# mouseaid.net
KiCad netlist of a schematic drawn in EAGLE
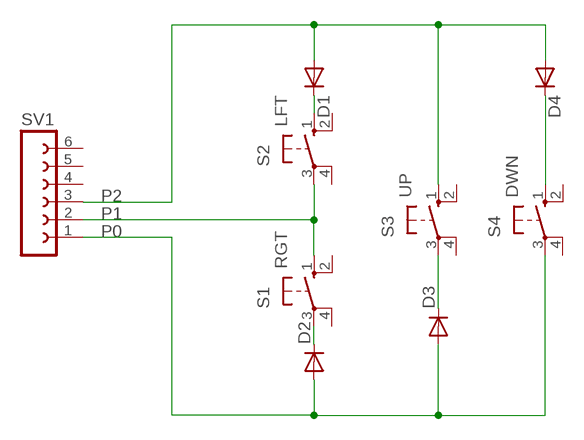
[diagram p0: schematic, sheet 1]

(export (version "E")
  (design (tool "Eeschema 10.0.6"))
  (components
    (comp (ref "D1")
      (value "DIODE-D-7.5")
      (footprint "eagle-import:D-7.5")
      (libsource (lib "eagle-import") (part "DIODE-D-7.5"))
    )
    (comp (ref "D2")
      (value "DIODE-D-7.5")
      (footprint "eagle-import:D-7.5")
      (libsource (lib "eagle-import") (part "DIODE-D-7.5"))
    )
    (comp (ref "D3")
      (value "DIODE-D-7.5")
      (footprint "eagle-import:D-7.5")
      (libsource (lib "eagle-import") (part "DIODE-D-7.5"))
    )
    (comp (ref "D4")
      (value "DIODE-D-7.5")
      (footprint "eagle-import:D-7.5")
      (libsource (lib "eagle-import") (part "DIODE-D-7.5"))
    )
    (comp (ref "S1")
      (value "RGT")
      (footprint "eagle-import:B3F-40XX")
      (fields (field (name "MF") "OMRON COMPONENTS USA") (field (name "MPN") "B3F-4000"))
      (libsource (lib "eagle-import") (part "40-XX"))
    )
    (comp (ref "S2")
      (value "LFT")
      (footprint "eagle-import:B3F-40XX")
      (fields (field (name "MF") "OMRON COMPONENTS USA") (field (name "MPN") "B3F-4000"))
      (libsource (lib "eagle-import") (part "40-XX"))
    )
    (comp (ref "S3")
      (value "UP")
      (footprint "eagle-import:B3F-40XX")
      (fields (field (name "MF") "OMRON COMPONENTS USA") (field (name "MPN") "B3F-4000"))
      (libsource (lib "eagle-import") (part "40-XX"))
    )
    (comp (ref "S4")
      (value "DWN")
      (footprint "eagle-import:B3F-40XX")
      (fields (field (name "MF") "OMRON COMPONENTS USA") (field (name "MPN") "B3F-4000"))
      (libsource (lib "eagle-import") (part "40-XX"))
    )
    (comp (ref "SV1")
      (value "FE06W")
      (footprint "eagle-import:FE06W")
      (libsource (lib "eagle-import") (part "FE06W"))
    )
  )
  (nets
    (net (code "1") (name "/P0") (class "Default")
      (node (ref "D2") (pin "A") (pinfunction "A_A") (pintype "passive"))
      (node (ref "D3") (pin "A") (pinfunction "A_A") (pintype "passive"))
      (node (ref "S4") (pin "3") (pinfunction "P_3") (pintype "passive"))
      (node (ref "SV1") (pin "1") (pinfunction "1_1") (pintype "passive"))
    )
    (net (code "2") (name "/P1") (class "Default")
      (node (ref "S1") (pin "1") (pinfunction "S_1") (pintype "passive"))
      (node (ref "S2") (pin "3") (pinfunction "P_3") (pintype "passive"))
      (node (ref "SV1") (pin "2") (pinfunction "2_2") (pintype "passive"))
    )
    (net (code "3") (name "/P2") (class "Default")
      (node (ref "D1") (pin "A") (pinfunction "A_A") (pintype "passive"))
      (node (ref "D4") (pin "A") (pinfunction "A_A") (pintype "passive"))
      (node (ref "S3") (pin "1") (pinfunction "S_1") (pintype "passive"))
      (node (ref "SV1") (pin "3") (pinfunction "3_3") (pintype "passive"))
    )
    (net (code "4") (name "Net-(S1-P)") (class "Default")
      (node (ref "D2") (pin "C") (pinfunction "C_C") (pintype "passive"))
      (node (ref "S1") (pin "3") (pinfunction "P_3") (pintype "passive"))
    )
    (net (code "5") (name "Net-(S2-S)") (class "Default")
      (node (ref "D1") (pin "C") (pinfunction "C_C") (pintype "passive"))
      (node (ref "S2") (pin "1") (pinfunction "S_1") (pintype "passive"))
    )
    (net (code "6") (name "Net-(S3-P)") (class "Default")
      (node (ref "D3") (pin "C") (pinfunction "C_C") (pintype "passive"))
      (node (ref "S3") (pin "3") (pinfunction "P_3") (pintype "passive"))
    )
    (net (code "7") (name "Net-(S4-S)") (class "Default")
      (node (ref "D4") (pin "C") (pinfunction "C_C") (pintype "passive"))
      (node (ref "S4") (pin "1") (pinfunction "S_1") (pintype "passive"))
    )
    (net (code "8") (name "unconnected-(S1-P1-Pad4)") (class "Default")
      (node (ref "S1") (pin "4") (pinfunction "P1_4") (pintype "passive"))
    )
    (net (code "9") (name "unconnected-(S1-S1-Pad2)") (class "Default")
      (node (ref "S1") (pin "2") (pinfunction "S1_2") (pintype "passive"))
    )
    (net (code "10") (name "unconnected-(S2-P1-Pad4)") (class "Default")
      (node (ref "S2") (pin "4") (pinfunction "P1_4") (pintype "passive"))
    )
    (net (code "11") (name "unconnected-(S2-S1-Pad2)") (class "Default")
      (node (ref "S2") (pin "2") (pinfunction "S1_2") (pintype "passive"))
    )
    (net (code "12") (name "unconnected-(S3-P1-Pad4)") (class "Default")
      (node (ref "S3") (pin "4") (pinfunction "P1_4") (pintype "passive"))
    )
    (net (code "13") (name "unconnected-(S3-S1-Pad2)") (class "Default")
      (node (ref "S3") (pin "2") (pinfunction "S1_2") (pintype "passive"))
    )
    (net (code "14") (name "unconnected-(S4-P1-Pad4)") (class "Default")
      (node (ref "S4") (pin "4") (pinfunction "P1_4") (pintype "passive"))
    )
    (net (code "15") (name "unconnected-(S4-S1-Pad2)") (class "Default")
      (node (ref "S4") (pin "2") (pinfunction "S1_2") (pintype "passive"))
    )
    (net (code "16") (name "unconnected-(SV1-Pad4)") (class "Default")
      (node (ref "SV1") (pin "4") (pinfunction "4_4") (pintype "passive"))
    )
    (net (code "17") (name "unconnected-(SV1-Pad5)") (class "Default")
      (node (ref "SV1") (pin "5") (pinfunction "5_5") (pintype "passive"))
    )
    (net (code "18") (name "unconnected-(SV1-Pad6)") (class "Default")
      (node (ref "SV1") (pin "6") (pinfunction "6_6") (pintype "passive"))
    )
  )
)
